# SCH_ROBOT_HUT_BUI.net
KiCad netlist of a schematic drawn in Altium Designer
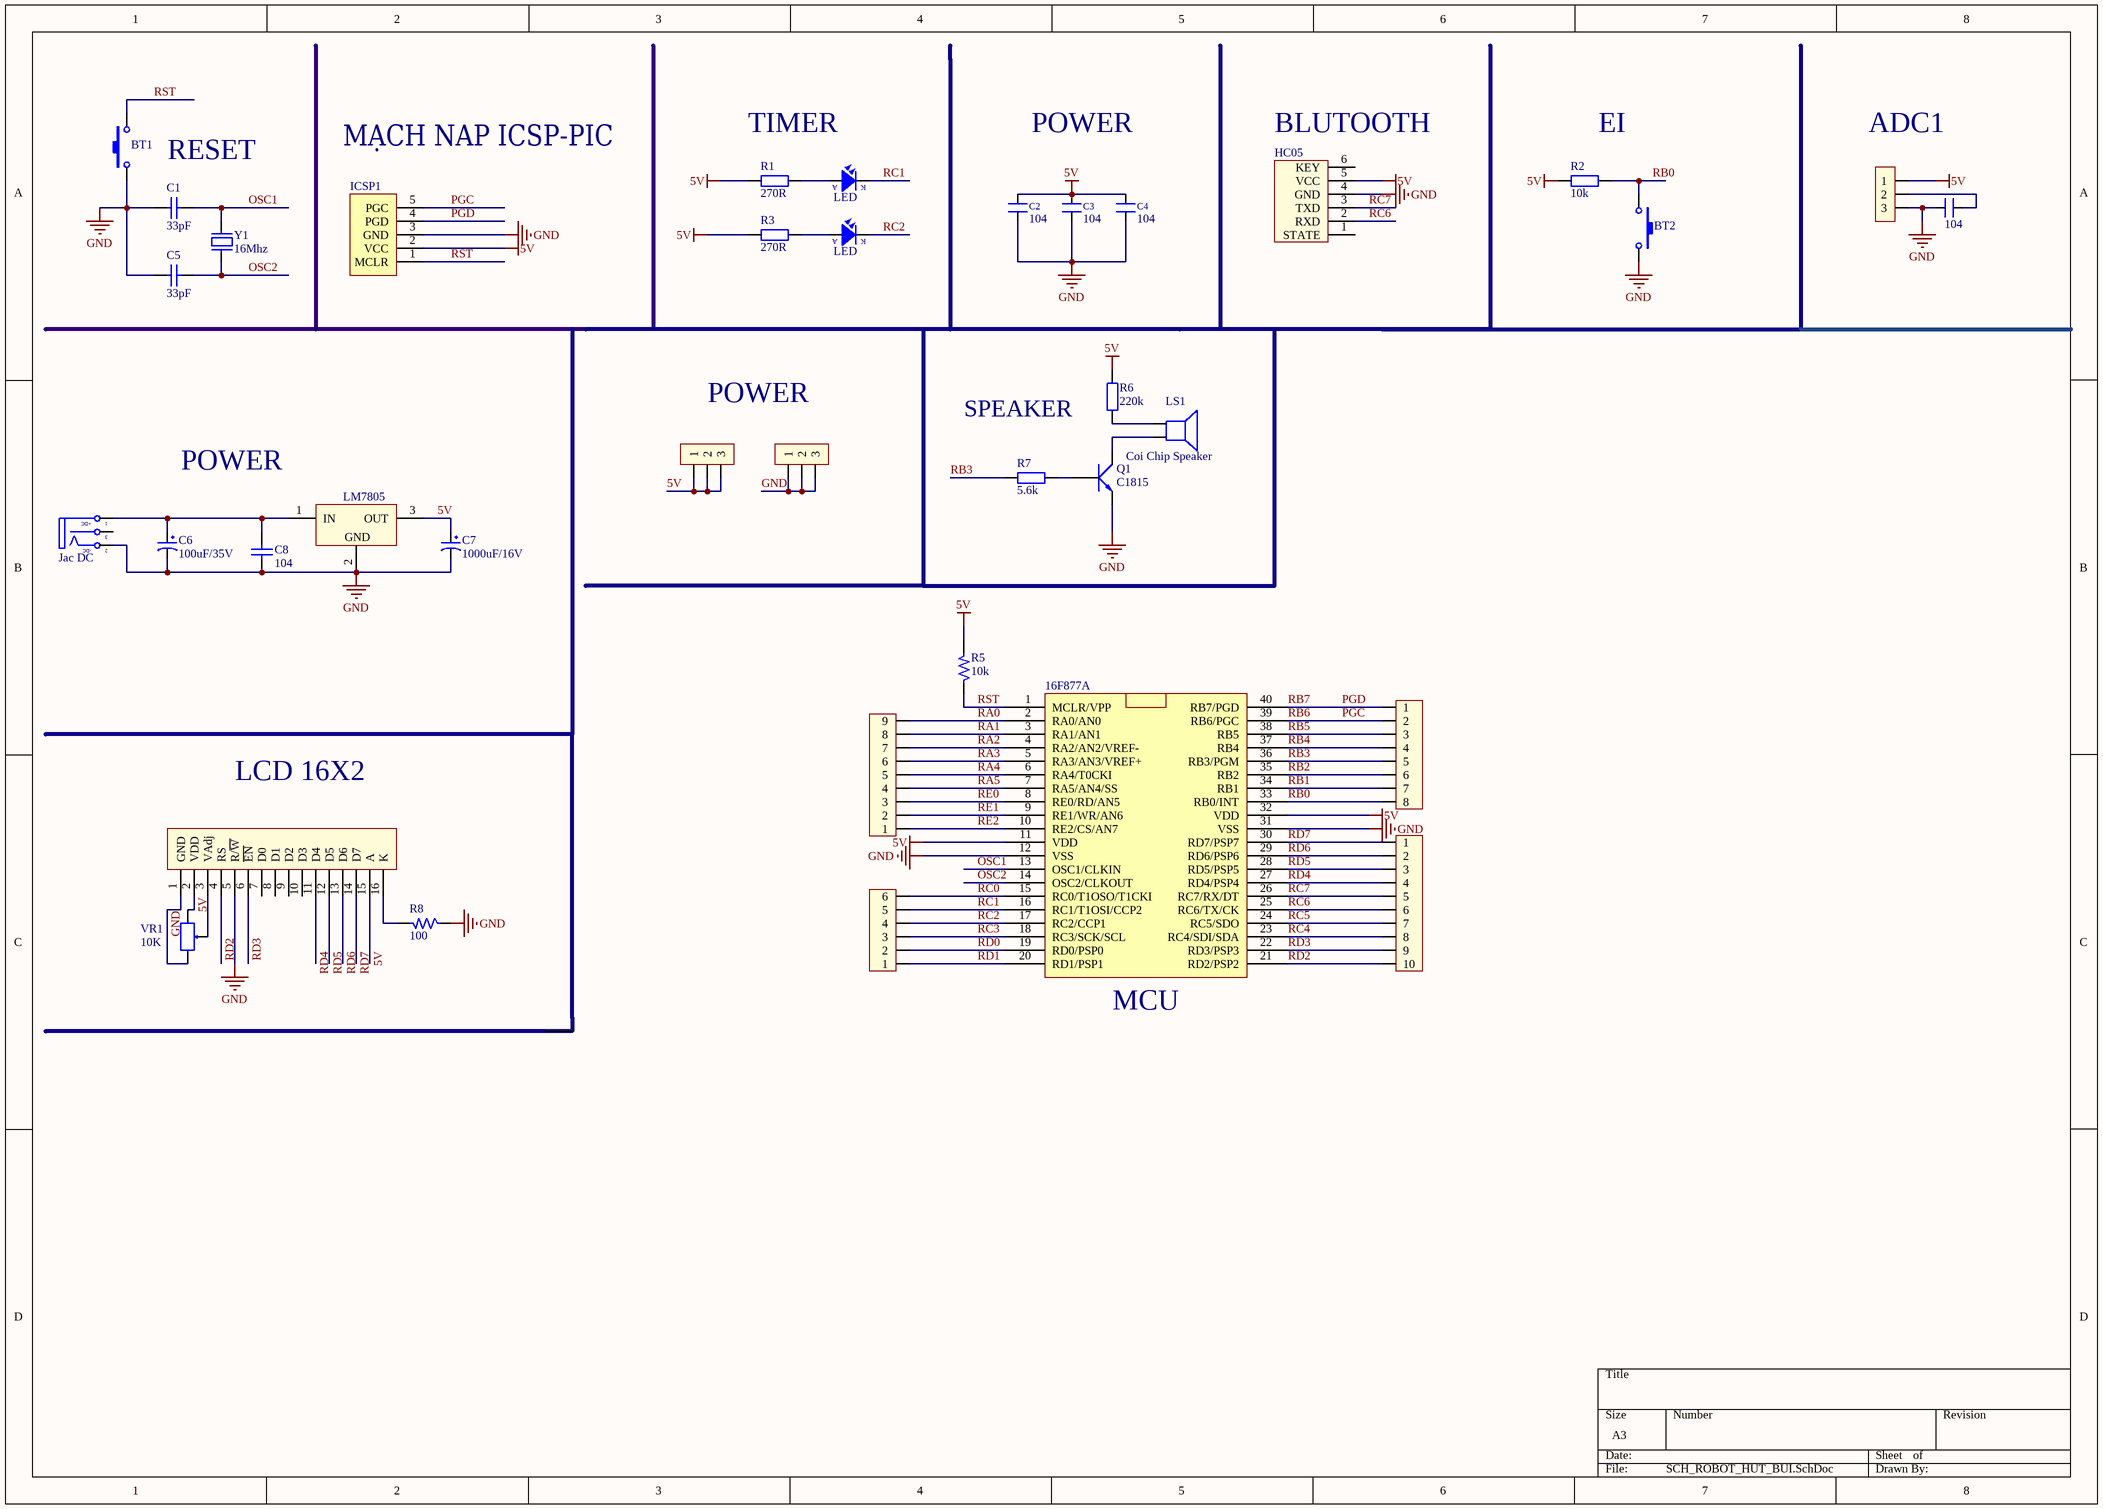
[diagram p0: SCH_ROBOT_HUT_BUI.SchDoc]

(export (version "E")
  (design (tool "Eeschema 10.0.6"))
  (components
    (comp (ref "ADC1") (value "Jumper 3") (footprint "JP3") (libsource (lib "") (part "JP3_1")))
    (comp (ref "BT1")
      (value "Nut Nhan 2 Chan SMD 3x6x2.5")
      (footprint "Nut Nhan 2 Chan SMD 3x6x2.5")
      (libsource (lib "Altium_Lib_HaDuyenDuc") (part "Nut Nhan 2 Chan SMD 3x6x2.5"))
    )
    (comp (ref "BT2")
      (value "Nut Nhan 2 Chan SMD 3x6x2.5")
      (footprint "Nut Nhan 2 Chan SMD 3x6x2.5")
      (libsource (lib "Altium_Lib_HaDuyenDuc") (part "Nut Nhan 2 Chan SMD 3x6x2.5"))
    )
    (comp (ref "C1")
      (value "33pF")
      (footprint "tu 0805")
      (description "Dán")
      (libsource (lib "Altium_Lib_by_KhueNguyenCreator") (part "Tu 0805 33pF 50V 10%"))
    )
    (comp (ref "C2")
      (value "104")
      (footprint "SM-CAP-0805")
      (fields (field (name "DESIGNED BY") "VanDungEvn"))
      (libsource (lib "my Library") (part "CAP SMD"))
    )
    (comp (ref "C3")
      (value "104")
      (footprint "SM-CAP-0805")
      (fields (field (name "DESIGNED BY") "VanDungEvn"))
      (libsource (lib "my Library") (part "CAP SMD"))
    )
    (comp (ref "C4")
      (value "104")
      (footprint "SM-CAP-0805")
      (fields (field (name "DESIGNED BY") "VanDungEvn"))
      (libsource (lib "my Library") (part "CAP SMD"))
    )
    (comp (ref "C5")
      (value "33pF")
      (footprint "tu 0805")
      (description "Dán")
      (libsource (lib "Altium_Lib_by_KhueNguyenCreator") (part "Tu 0805 33pF 50V 10%"))
    )
    (comp (ref "C6")
      (value "100uF/35V")
      (footprint "CP1.5/3.4")
      (description "Cap 100uF/35V - 470uF/16V")
      (libsource (lib "syhaunguyen") (part "CP3"))
    )
    (comp (ref "C7")
      (value "1000uF/16V")
      (footprint "CP1.5/3.4")
      (description "Cap 1000uF/16V - 220uF/50V")
      (libsource (lib "syhaunguyen") (part "CP4"))
    )
    (comp (ref "C8")
      (value "104")
      (footprint "tu 0805")
      (description "Dán")
      (libsource (lib "Altium_Lib_by_KhueNguyenCreator") (part "Tu 0805 104 50V 10%"))
    )
    (comp (ref "C9")
      (value "104")
      (footprint "SM-CAP-0805")
      (fields (field (name "DESIGNED BY") "VanDungEvn"))
      (libsource (lib "my Library") (part "CAP SMD"))
    )
    (comp (ref "HC05")
      (value "HC05 Bluetooth")
      (footprint "HC05 Bluethooth Nam")
      (description "Bluetooth HC05")
      (libsource (lib "Altium_Lib_HaDuyenDuc") (part "HC05 Bluetooth"))
    )
    (comp (ref "IC1")
      (value "LM7805")
      (footprint "QTO-220")
      (description "On ap +, from + 5 to + 24VDC")
      (libsource (lib "my Library") (part "LM78xx"))
    )
    (comp (ref "IC2")
      (value "16F877A")
      (footprint "DIP40/W0.6")
      (libsource (lib "my Library") (part "PIC 16F877A"))
    )
    (comp (ref "ICSP1")
      (value "ICSP-PIC")
      (footprint "HDR1X5")
      (description "Header, 5-Pin")
      (fields (field (name "PUBLISHER") "Altium Limited"))
      (libsource (lib "my Library") (part "ICSP-PIC"))
    )
    (comp (ref "J1") (value "Jumper 3") (footprint "JP3") (libsource (lib "syhaunguyen") (part "JP3")))
    (comp (ref "J3") (value "Jumper 3") (footprint "JP3") (libsource (lib "syhaunguyen") (part "JP3")))
    (comp (ref "JDC1")
      (value "Jac DC")
      (footprint "DC-IN")
      (description "Jac DC input")
      (libsource (lib "syhaunguyen") (part "DCIN"))
    )
    (comp (ref "JP1")
      (value "JP8")
      (footprint "CON8")
      (description "Connector 8")
      (libsource (lib "my Library") (part "Con8"))
    )
    (comp (ref "JP2")
      (value "connector")
      (footprint "con9")
      (description "connector 9")
      (libsource (lib "my Library") (part "Con9"))
    )
    (comp (ref "JP3")
      (value "JP10")
      (footprint "CON10")
      (description "Connector 10")
      (libsource (lib "syhaunguyen") (part "Con10"))
    )
    (comp (ref "JP4")
      (value "JP6")
      (footprint "CON6")
      (description "Connector 6")
      (libsource (lib "my Library") (part "Con6"))
    )
    (comp (ref "LCD1")
      (value "LCD1602 XL")
      (footprint "LCD1602 with Jump")
      (description "LCD 1602 Xanh Lá")
      (libsource (lib "Altium_Lib_by_KhueNguyenCreator") (part "LCD1602 XL"))
    )
    (comp (ref "LED1")
      (value "LED")
      (footprint "LED-3")
      (description "LED Single colour Green and Red")
      (libsource (lib "my Library") (part "LED"))
    )
    (comp (ref "LED2")
      (value "LED")
      (footprint "LED-3")
      (description "LED Single colour Green and Red")
      (libsource (lib "my Library") (part "LED"))
    )
    (comp (ref "LS1")
      (value "Coi Chip Speaker")
      (footprint "Coi Chip Speacker")
      (description "Còi chip")
      (libsource (lib "Altium_Lib_by_KhueNguyenCreator") (part "Coi Chip Speaker"))
    )
    (comp (ref "Q1")
      (value "C1815")
      (footprint "TO92")
      (description "NPN transistor")
      (libsource (lib "Altium_Lib_by_KhueNguyenCreator") (part "C1815"))
    )
    (comp (ref "R1")
      (value "270R")
      (footprint "tro vach 1/4w")
      (description "Cắm")
      (libsource (lib "Altium_Lib_by_KhueNguyenCreator") (part "Tro Vach 1/4W 5% 270R"))
    )
    (comp (ref "R2")
      (value "10k")
      (footprint "tro vach 1/4w")
      (description "Cắm")
      (libsource (lib "Altium_Lib_by_KhueNguyenCreator") (part "Tro Vach 1/4W 1% 10k"))
    )
    (comp (ref "R3")
      (value "270R")
      (footprint "tro vach 1/4w")
      (description "Cắm")
      (libsource (lib "Altium_Lib_by_KhueNguyenCreator") (part "Tro Vach 1/4W 5% 270R"))
    )
    (comp (ref "R5")
      (value "10k")
      (footprint "R1/4W")
      (description "Res")
      (libsource (lib "my Library") (part "Res"))
    )
    (comp (ref "R6")
      (value "220k")
      (footprint "tro vach 1/2w")
      (description "Cắm")
      (libsource (lib "Altium_Lib_by_KhueNguyenCreator") (part "Tro Vach 1/2W 5% 220k"))
    )
    (comp (ref "R7")
      (value "5.6k")
      (footprint "tro vach 1/4w")
      (description "Cắm")
      (libsource (lib "Altium_Lib_by_KhueNguyenCreator") (part "Tro Vach 1/4W 5% 5.6k"))
    )
    (comp (ref "R8")
      (value "100")
      (footprint "SM-RES-1206")
      (description "Resistor 1/4W")
      (libsource (lib "syhaunguyen") (part "R"))
    )
    (comp (ref "VR1")
      (value "10K")
      (footprint "VR")
      (description "Var Resistor")
      (libsource (lib "syhaunguyen") (part "VR"))
    )
    (comp (ref "Y1")
      (value "16Mhz")
      (footprint "Thach Anh 2 chan SMD")
      (description "Crystal For all Crystal 2pin.")
      (libsource (lib "Altium_Lib_by_KhueNguyenCreator") (part "Thach Anh 2 chan SMD"))
    )
  )
  (nets
    (net (code "1") (name "/OSC1") (class "Default")
      (node (ref "C1") (pin "1") (pinfunction "1_1") (pintype "passive"))
      (node (ref "IC2") (pin "13") (pinfunction "OSC1/CLKIN_13") (pintype "passive"))
      (node (ref "Y1") (pin "2") (pinfunction "2_2") (pintype "passive"))
    )
    (net (code "2") (name "/OSC2") (class "Default")
      (node (ref "C5") (pin "1") (pinfunction "1_1") (pintype "passive"))
      (node (ref "IC2") (pin "14") (pinfunction "OSC2/CLKOUT_14") (pintype "passive"))
      (node (ref "Y1") (pin "1") (pinfunction "1_1") (pintype "passive"))
    )
    (net (code "3") (name "/PGC") (class "Default")
      (node (ref "IC2") (pin "39") (pinfunction "RB6/PGC_39") (pintype "passive"))
      (node (ref "ICSP1") (pin "5") (pinfunction "PGC_5") (pintype "passive"))
      (node (ref "JP1") (pin "2") (pinfunction "2_2") (pintype "passive"))
    )
    (net (code "4") (name "/PGD") (class "Default")
      (node (ref "IC2") (pin "40") (pinfunction "RB7/PGD_40") (pintype "passive"))
      (node (ref "ICSP1") (pin "4") (pinfunction "PGD_4") (pintype "passive"))
      (node (ref "JP1") (pin "1") (pinfunction "1_1") (pintype "passive"))
    )
    (net (code "5") (name "/RA0") (class "Default")
      (node (ref "IC2") (pin "2") (pinfunction "RA0/AN0_2") (pintype "passive"))
      (node (ref "JP2") (pin "9") (pinfunction "9_9") (pintype "passive"))
    )
    (net (code "6") (name "/RA1") (class "Default")
      (node (ref "IC2") (pin "3") (pinfunction "RA1/AN1_3") (pintype "passive"))
      (node (ref "JP2") (pin "8") (pinfunction "8_8") (pintype "passive"))
    )
    (net (code "7") (name "/RA2") (class "Default")
      (node (ref "IC2") (pin "4") (pinfunction "RA2/AN2/VREF-_4") (pintype "passive"))
      (node (ref "JP2") (pin "7") (pinfunction "7_7") (pintype "passive"))
    )
    (net (code "8") (name "/RA3") (class "Default")
      (node (ref "IC2") (pin "5") (pinfunction "RA3/AN3/VREF+_5") (pintype "passive"))
      (node (ref "JP2") (pin "6") (pinfunction "6_6") (pintype "passive"))
    )
    (net (code "9") (name "/RA4") (class "Default")
      (node (ref "IC2") (pin "6") (pinfunction "RA4/T0CKI_6") (pintype "passive"))
      (node (ref "JP2") (pin "5") (pinfunction "5_5") (pintype "passive"))
    )
    (net (code "10") (name "/RA5") (class "Default")
      (node (ref "IC2") (pin "7") (pinfunction "RA5/AN4/SS_7") (pintype "passive"))
      (node (ref "JP2") (pin "4") (pinfunction "4_4") (pintype "passive"))
    )
    (net (code "11") (name "/RB0") (class "Default")
      (node (ref "BT2") (pin "1") (pinfunction "1_1") (pintype "passive"))
      (node (ref "IC2") (pin "33") (pinfunction "RB0/INT_33") (pintype "passive"))
      (node (ref "JP1") (pin "8") (pinfunction "8_8") (pintype "passive"))
      (node (ref "R2") (pin "2") (pinfunction "2_2") (pintype "passive"))
    )
    (net (code "12") (name "/RB1") (class "Default")
      (node (ref "IC2") (pin "34") (pinfunction "RB1_34") (pintype "passive"))
      (node (ref "JP1") (pin "7") (pinfunction "7_7") (pintype "passive"))
    )
    (net (code "13") (name "/RB2") (class "Default")
      (node (ref "IC2") (pin "35") (pinfunction "RB2_35") (pintype "passive"))
      (node (ref "JP1") (pin "6") (pinfunction "6_6") (pintype "passive"))
    )
    (net (code "14") (name "/RB3") (class "Default")
      (node (ref "IC2") (pin "36") (pinfunction "RB3/PGM_36") (pintype "passive"))
      (node (ref "JP1") (pin "5") (pinfunction "5_5") (pintype "passive"))
      (node (ref "R7") (pin "1") (pinfunction "1_1") (pintype "passive"))
    )
    (net (code "15") (name "/RB4") (class "Default")
      (node (ref "IC2") (pin "37") (pinfunction "RB4_37") (pintype "passive"))
      (node (ref "JP1") (pin "4") (pinfunction "4_4") (pintype "passive"))
    )
    (net (code "16") (name "/RB5") (class "Default")
      (node (ref "IC2") (pin "38") (pinfunction "RB5_38") (pintype "passive"))
      (node (ref "JP1") (pin "3") (pinfunction "3_3") (pintype "passive"))
    )
    (net (code "17") (name "/RC0") (class "Default")
      (node (ref "IC2") (pin "15") (pinfunction "RC0/T1OSO/T1CKI_15") (pintype "passive"))
      (node (ref "JP4") (pin "6") (pinfunction "6_6") (pintype "passive"))
    )
    (net (code "18") (name "/RC1") (class "Default")
      (node (ref "IC2") (pin "16") (pinfunction "RC1/T1OSI/CCP2_16") (pintype "passive"))
      (node (ref "JP4") (pin "5") (pinfunction "5_5") (pintype "passive"))
      (node (ref "LED1") (pin "2") (pinfunction "K_2") (pintype "passive"))
    )
    (net (code "19") (name "/RC2") (class "Default")
      (node (ref "IC2") (pin "17") (pinfunction "RC2/CCP1_17") (pintype "passive"))
      (node (ref "JP4") (pin "4") (pinfunction "4_4") (pintype "passive"))
      (node (ref "LED2") (pin "2") (pinfunction "K_2") (pintype "passive"))
    )
    (net (code "20") (name "/RC3") (class "Default")
      (node (ref "IC2") (pin "18") (pinfunction "RC3/SCK/SCL_18") (pintype "passive"))
      (node (ref "JP4") (pin "3") (pinfunction "3_3") (pintype "passive"))
    )
    (net (code "21") (name "/RC4") (class "Default")
      (node (ref "IC2") (pin "23") (pinfunction "RC4/SDI/SDA_23") (pintype "passive"))
      (node (ref "JP3") (pin "8") (pinfunction "8_8") (pintype "passive"))
    )
    (net (code "22") (name "/RC5") (class "Default")
      (node (ref "IC2") (pin "24") (pinfunction "RC5/SDO_24") (pintype "passive"))
      (node (ref "JP3") (pin "7") (pinfunction "7_7") (pintype "passive"))
    )
    (net (code "23") (name "/RC6") (class "Default")
      (node (ref "HC05") (pin "2") (pinfunction "RXD_2") (pintype "passive"))
      (node (ref "IC2") (pin "25") (pinfunction "RC6/TX/CK_25") (pintype "passive"))
      (node (ref "JP3") (pin "6") (pinfunction "6_6") (pintype "passive"))
    )
    (net (code "24") (name "/RC7") (class "Default")
      (node (ref "HC05") (pin "3") (pinfunction "TXD_3") (pintype "passive"))
      (node (ref "IC2") (pin "26") (pinfunction "RC7/RX/DT_26") (pintype "passive"))
      (node (ref "JP3") (pin "5") (pinfunction "5_5") (pintype "passive"))
    )
    (net (code "25") (name "/RD0") (class "Default")
      (node (ref "IC2") (pin "19") (pinfunction "RD0/PSP0_19") (pintype "passive"))
      (node (ref "JP4") (pin "2") (pinfunction "2_2") (pintype "passive"))
    )
    (net (code "26") (name "/RD1") (class "Default")
      (node (ref "IC2") (pin "20") (pinfunction "RD1/PSP1_20") (pintype "passive"))
      (node (ref "JP4") (pin "1") (pinfunction "1_1") (pintype "passive"))
    )
    (net (code "27") (name "/RD2") (class "Default")
      (node (ref "IC2") (pin "21") (pinfunction "RD2/PSP2_21") (pintype "passive"))
      (node (ref "JP3") (pin "10") (pinfunction "10_10") (pintype "passive"))
      (node (ref "LCD1") (pin "4") (pinfunction "RS_4") (pintype "passive"))
    )
    (net (code "28") (name "/RD3") (class "Default")
      (node (ref "IC2") (pin "22") (pinfunction "RD3/PSP3_22") (pintype "passive"))
      (node (ref "JP3") (pin "9") (pinfunction "9_9") (pintype "passive"))
      (node (ref "LCD1") (pin "6") (pinfunction "~{EN}_6") (pintype "passive"))
    )
    (net (code "29") (name "/RD4") (class "Default")
      (node (ref "IC2") (pin "27") (pinfunction "RD4/PSP4_27") (pintype "passive"))
      (node (ref "JP3") (pin "4") (pinfunction "4_4") (pintype "passive"))
      (node (ref "LCD1") (pin "11") (pinfunction "D4_11") (pintype "passive"))
    )
    (net (code "30") (name "/RD5") (class "Default")
      (node (ref "IC2") (pin "28") (pinfunction "RD5/PSP5_28") (pintype "passive"))
      (node (ref "JP3") (pin "3") (pinfunction "3_3") (pintype "passive"))
      (node (ref "LCD1") (pin "12") (pinfunction "D5_12") (pintype "passive"))
    )
    (net (code "31") (name "/RD6") (class "Default")
      (node (ref "IC2") (pin "29") (pinfunction "RD6/PSP6_29") (pintype "passive"))
      (node (ref "JP3") (pin "2") (pinfunction "2_2") (pintype "passive"))
      (node (ref "LCD1") (pin "13") (pinfunction "D6_13") (pintype "passive"))
    )
    (net (code "32") (name "/RD7") (class "Default")
      (node (ref "IC2") (pin "30") (pinfunction "RD7/PSP7_30") (pintype "passive"))
      (node (ref "JP3") (pin "1") (pinfunction "1_1") (pintype "passive"))
      (node (ref "LCD1") (pin "14") (pinfunction "D7_14") (pintype "passive"))
    )
    (net (code "33") (name "/RE0") (class "Default")
      (node (ref "IC2") (pin "8") (pinfunction "RE0/RD/AN5_8") (pintype "passive"))
      (node (ref "JP2") (pin "3") (pinfunction "3_3") (pintype "passive"))
    )
    (net (code "34") (name "/RE1") (class "Default")
      (node (ref "IC2") (pin "9") (pinfunction "RE1/WR/AN6_9") (pintype "passive"))
      (node (ref "JP2") (pin "2") (pinfunction "2_2") (pintype "passive"))
    )
    (net (code "35") (name "/RE2") (class "Default")
      (node (ref "IC2") (pin "10") (pinfunction "RE2/CS/AN7_10") (pintype "passive"))
      (node (ref "JP2") (pin "1") (pinfunction "1_1") (pintype "passive"))
    )
    (net (code "36") (name "/RST") (class "Default")
      (node (ref "BT1") (pin "2") (pinfunction "2_2") (pintype "passive"))
      (node (ref "IC2") (pin "1") (pinfunction "MCLR/VPP_1") (pintype "passive"))
      (node (ref "ICSP1") (pin "1") (pinfunction "MCLR_1") (pintype "passive"))
      (node (ref "R5") (pin "1") (pinfunction "1_1") (pintype "passive"))
    )
    (net (code "37") (name "5V") (class "Default")
      (node (ref "ADC1") (pin "1") (pinfunction "1_1") (pintype "passive"))
      (node (ref "C2") (pin "2") (pinfunction "2_2") (pintype "passive"))
      (node (ref "C3") (pin "2") (pinfunction "2_2") (pintype "passive"))
      (node (ref "C4") (pin "2") (pinfunction "2_2") (pintype "passive"))
      (node (ref "C7") (pin "1") (pinfunction "1_1") (pintype "passive"))
      (node (ref "HC05") (pin "5") (pinfunction "VCC_5") (pintype "passive"))
      (node (ref "IC1") (pin "3") (pinfunction "OUT_3") (pintype "passive"))
      (node (ref "IC2") (pin "11") (pinfunction "VDD_11") (pintype "passive"))
      (node (ref "IC2") (pin "32") (pinfunction "VDD_32") (pintype "passive"))
      (node (ref "ICSP1") (pin "2") (pinfunction "VCC_2") (pintype "passive"))
      (node (ref "J1") (pin "1") (pinfunction "1_1") (pintype "passive"))
      (node (ref "J1") (pin "2") (pinfunction "2_2") (pintype "passive"))
      (node (ref "J1") (pin "3") (pinfunction "3_3") (pintype "passive"))
      (node (ref "LCD1") (pin "15") (pinfunction "A_15") (pintype "passive"))
      (node (ref "LCD1") (pin "2") (pinfunction "VDD_2") (pintype "passive"))
      (node (ref "R1") (pin "1") (pinfunction "1_1") (pintype "passive"))
      (node (ref "R2") (pin "1") (pinfunction "1_1") (pintype "passive"))
      (node (ref "R3") (pin "1") (pinfunction "1_1") (pintype "passive"))
      (node (ref "R5") (pin "2") (pinfunction "2_2") (pintype "passive"))
      (node (ref "R6") (pin "2") (pinfunction "2_2") (pintype "passive"))
      (node (ref "VR1") (pin "1") (pinfunction "1_1") (pintype "passive"))
    )
    (net (code "38") (name "GND") (class "Default")
      (node (ref "ADC1") (pin "3") (pinfunction "3_3") (pintype "passive"))
      (node (ref "BT1") (pin "1") (pinfunction "1_1") (pintype "passive"))
      (node (ref "BT2") (pin "2") (pinfunction "2_2") (pintype "passive"))
      (node (ref "C1") (pin "2") (pinfunction "2_2") (pintype "passive"))
      (node (ref "C2") (pin "1") (pinfunction "1_1") (pintype "passive"))
      (node (ref "C3") (pin "1") (pinfunction "1_1") (pintype "passive"))
      (node (ref "C4") (pin "1") (pinfunction "1_1") (pintype "passive"))
      (node (ref "C5") (pin "2") (pinfunction "2_2") (pintype "passive"))
      (node (ref "C6") (pin "2") (pinfunction "2_2") (pintype "passive"))
      (node (ref "C7") (pin "2") (pinfunction "2_2") (pintype "passive"))
      (node (ref "C8") (pin "2") (pinfunction "2_2") (pintype "passive"))
      (node (ref "C9") (pin "1") (pinfunction "1_1") (pintype "passive"))
      (node (ref "HC05") (pin "4") (pinfunction "GND_4") (pintype "passive"))
      (node (ref "IC1") (pin "2") (pinfunction "GND_2") (pintype "passive"))
      (node (ref "IC2") (pin "12") (pinfunction "VSS_12") (pintype "passive"))
      (node (ref "IC2") (pin "31") (pinfunction "VSS_31") (pintype "passive"))
      (node (ref "ICSP1") (pin "3") (pinfunction "GND_3") (pintype "passive"))
      (node (ref "J3") (pin "1") (pinfunction "1_1") (pintype "passive"))
      (node (ref "J3") (pin "2") (pinfunction "2_2") (pintype "passive"))
      (node (ref "J3") (pin "3") (pinfunction "3_3") (pintype "passive"))
      (node (ref "JDC1") (pin "2") (pinfunction "TN_2") (pintype "passive"))
      (node (ref "LCD1") (pin "1") (pinfunction "GND_1") (pintype "passive"))
      (node (ref "LCD1") (pin "5") (pinfunction "R/~{W}_5") (pintype "passive"))
      (node (ref "Q1") (pin "1") (pinfunction "E_1") (pintype "passive"))
      (node (ref "R8") (pin "1") (pinfunction "1_1") (pintype "passive"))
      (node (ref "VR1") (pin "3") (pinfunction "3_3") (pintype "passive"))
    )
    (net (code "39") (name "Net-(ADC1-Pad2)") (class "Default")
      (node (ref "ADC1") (pin "2") (pinfunction "2_2") (pintype "passive"))
      (node (ref "C9") (pin "2") (pinfunction "2_2") (pintype "passive"))
    )
    (net (code "40") (name "Net-(IC1-IN)") (class "Default")
      (node (ref "C6") (pin "1") (pinfunction "1_1") (pintype "passive"))
      (node (ref "C8") (pin "1") (pinfunction "1_1") (pintype "passive"))
      (node (ref "IC1") (pin "1") (pinfunction "IN_1") (pintype "passive"))
      (node (ref "JDC1") (pin "1") (pinfunction "T_1") (pintype "passive"))
    )
    (net (code "41") (name "Net-(LCD1-K)") (class "Default")
      (node (ref "LCD1") (pin "16") (pinfunction "K_16") (pintype "passive"))
      (node (ref "R8") (pin "2") (pinfunction "2_2") (pintype "passive"))
    )
    (net (code "42") (name "Net-(LCD1-VAdj)") (class "Default")
      (node (ref "LCD1") (pin "3") (pinfunction "VAdj_3") (pintype "passive"))
      (node (ref "VR1") (pin "2") (pinfunction "2_2") (pintype "passive"))
    )
    (net (code "43") (name "Net-(LED1-A)") (class "Default")
      (node (ref "LED1") (pin "1") (pinfunction "A_1") (pintype "passive"))
      (node (ref "R1") (pin "2") (pinfunction "2_2") (pintype "passive"))
    )
    (net (code "44") (name "Net-(LED2-A)") (class "Default")
      (node (ref "LED2") (pin "1") (pinfunction "A_1") (pintype "passive"))
      (node (ref "R3") (pin "2") (pinfunction "2_2") (pintype "passive"))
    )
    (net (code "45") (name "Net-(LS1-Pad1)") (class "Default")
      (node (ref "LS1") (pin "1") (pinfunction "1_1") (pintype "passive"))
      (node (ref "R6") (pin "1") (pinfunction "1_1") (pintype "passive"))
    )
    (net (code "46") (name "Net-(Q1-B)") (class "Default")
      (node (ref "Q1") (pin "3") (pinfunction "B_3") (pintype "passive"))
      (node (ref "R7") (pin "2") (pinfunction "2_2") (pintype "passive"))
    )
    (net (code "47") (name "Net-(Q1-C)") (class "Default")
      (node (ref "LS1") (pin "2") (pinfunction "2_2") (pintype "passive"))
      (node (ref "Q1") (pin "2") (pinfunction "C_2") (pintype "passive"))
    )
    (net (code "48") (name "unconnected-(HC05-KEY-Pad6)") (class "Default")
      (node (ref "HC05") (pin "6") (pinfunction "KEY_6") (pintype "passive"))
    )
    (net (code "49") (name "unconnected-(HC05-STATE-Pad1)") (class "Default")
      (node (ref "HC05") (pin "1") (pinfunction "STATE_1") (pintype "passive"))
    )
    (net (code "50") (name "unconnected-(JDC1-S-Pad3)") (class "Default")
      (node (ref "JDC1") (pin "3") (pinfunction "S_3") (pintype "power_in"))
    )
    (net (code "51") (name "unconnected-(LCD1-D0-Pad7)") (class "Default")
      (node (ref "LCD1") (pin "7") (pinfunction "D0_7") (pintype "passive"))
    )
    (net (code "52") (name "unconnected-(LCD1-D1-Pad8)") (class "Default")
      (node (ref "LCD1") (pin "8") (pinfunction "D1_8") (pintype "passive"))
    )
    (net (code "53") (name "unconnected-(LCD1-D2-Pad9)") (class "Default")
      (node (ref "LCD1") (pin "9") (pinfunction "D2_9") (pintype "passive"))
    )
    (net (code "54") (name "unconnected-(LCD1-D3-Pad10)") (class "Default")
      (node (ref "LCD1") (pin "10") (pinfunction "D3_10") (pintype "passive"))
    )
  )
)
